# LED_servo_board.net
KiCad netlist of a schematic drawn in EAGLE
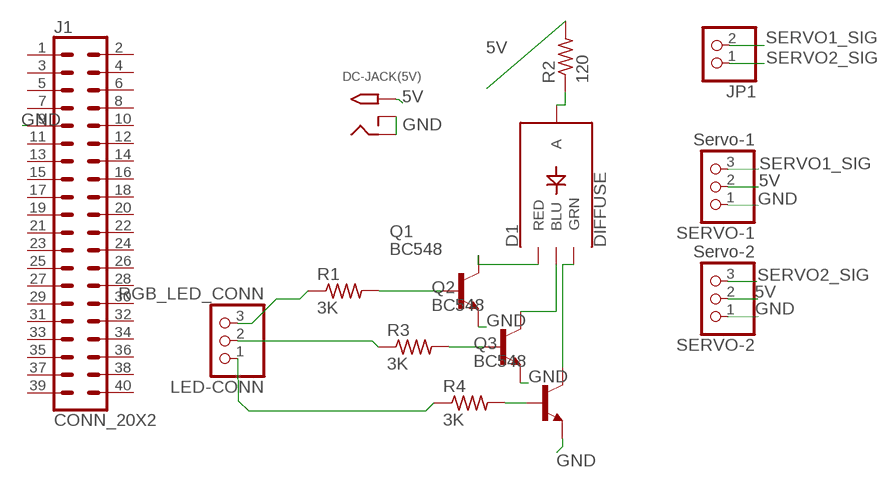
[diagram p0: schematic, sheet 1]

(export (version "E")
  (design (tool "Eeschema 10.0.6"))
  (components
    (comp (ref "D1")
      (value "DIFFUSE")
      (footprint "eagle-import:LED-RGB-THRU")
      (libsource (lib "eagle-import") (part "LED-RGB-CADIFFUSE"))
    )
    (comp (ref "DC-JACK(5V)")
      (value "2.1MMJACKTHM")
      (footprint "eagle-import:PJ-102A")
      (libsource (lib "eagle-import") (part "2.1MMJACKTHM"))
    )
    (comp (ref "J1")
      (value "CONN_20X2")
      (footprint "eagle-import:2X20")
      (libsource (lib "eagle-import") (part "CONN_20X2"))
    )
    (comp (ref "JP1")
      (value "PINHD-1X2")
      (footprint "eagle-import:1X02")
      (libsource (lib "eagle-import") (part "PINHD-1X2"))
    )
    (comp (ref "LED-CONN")
      (value "RGB_LED_CONN")
      (footprint "eagle-import:1X03")
      (libsource (lib "eagle-import") (part "PINHD-1X3"))
    )
    (comp (ref "Q1")
      (value "BC548")
      (footprint "eagle-import:TO92-EBC")
      (libsource (lib "eagle-import") (part "BC548"))
    )
    (comp (ref "Q2")
      (value "BC548")
      (footprint "eagle-import:TO92-EBC")
      (libsource (lib "eagle-import") (part "BC548"))
    )
    (comp (ref "Q3")
      (value "BC548")
      (footprint "eagle-import:TO92-EBC")
      (libsource (lib "eagle-import") (part "BC548"))
    )
    (comp (ref "R1")
      (value "3K")
      (footprint "eagle-import:0204_5")
      (libsource (lib "eagle-import") (part "R-US_0204/5"))
    )
    (comp (ref "R2")
      (value "120")
      (footprint "eagle-import:0204_5")
      (libsource (lib "eagle-import") (part "R-US_0204/5"))
    )
    (comp (ref "R3")
      (value "3K")
      (footprint "eagle-import:0204_5")
      (libsource (lib "eagle-import") (part "R-US_0204/5"))
    )
    (comp (ref "R4")
      (value "3K")
      (footprint "eagle-import:0204_5")
      (libsource (lib "eagle-import") (part "R-US_0204/5"))
    )
    (comp (ref "SERVO-1")
      (value "Servo-1")
      (footprint "eagle-import:1X03")
      (libsource (lib "eagle-import") (part "PINHD-1X3"))
    )
    (comp (ref "SERVO-2")
      (value "Servo-2")
      (footprint "eagle-import:1X03")
      (libsource (lib "eagle-import") (part "PINHD-1X3"))
    )
  )
  (nets
    (net (code "1") (name "/5V") (class "Default")
      (node (ref "DC-JACK(5V)") (pin "TIP") (pinfunction "TIP_TIP") (pintype "bidirectional"))
      (node (ref "R2") (pin "2") (pinfunction "2_2") (pintype "passive"))
      (node (ref "SERVO-1") (pin "2") (pinfunction "2_2") (pintype "passive"))
      (node (ref "SERVO-2") (pin "2") (pinfunction "2_2") (pintype "passive"))
    )
    (net (code "2") (name "/GND") (class "Default")
      (node (ref "DC-JACK(5V)") (pin "RING") (pinfunction "RING_RING") (pintype "bidirectional"))
      (node (ref "DC-JACK(5V)") (pin "RING_SW") (pinfunction "RING_SW_RING_SW") (pintype "bidirectional"))
      (node (ref "J1") (pin "9") (pinfunction "9_9") (pintype "passive"))
      (node (ref "Q1") (pin "E") (pinfunction "E_E") (pintype "passive"))
      (node (ref "Q2") (pin "E") (pinfunction "E_E") (pintype "passive"))
      (node (ref "Q3") (pin "E") (pinfunction "E_E") (pintype "passive"))
      (node (ref "SERVO-1") (pin "1") (pinfunction "1_1") (pintype "passive"))
      (node (ref "SERVO-2") (pin "1") (pinfunction "1_1") (pintype "passive"))
    )
    (net (code "3") (name "/SERVO1_SIG") (class "Default")
      (node (ref "JP1") (pin "2") (pinfunction "2_2") (pintype "passive"))
      (node (ref "SERVO-1") (pin "3") (pinfunction "3_3") (pintype "passive"))
    )
    (net (code "4") (name "/SERVO2_SIG") (class "Default")
      (node (ref "JP1") (pin "1") (pinfunction "1_1") (pintype "passive"))
      (node (ref "SERVO-2") (pin "3") (pinfunction "3_3") (pintype "passive"))
    )
    (net (code "5") (name "Net-(D1-A)") (class "Default")
      (node (ref "D1") (pin "2") (pinfunction "A_2") (pintype "bidirectional"))
      (node (ref "R2") (pin "1") (pinfunction "1_1") (pintype "passive"))
    )
    (net (code "6") (name "Net-(D1-BLU)") (class "Default")
      (node (ref "D1") (pin "4") (pinfunction "BLU_4") (pintype "bidirectional"))
      (node (ref "Q2") (pin "C") (pinfunction "C_C") (pintype "passive"))
    )
    (net (code "7") (name "Net-(D1-GRN)") (class "Default")
      (node (ref "D1") (pin "3") (pinfunction "GRN_3") (pintype "bidirectional"))
      (node (ref "Q3") (pin "C") (pinfunction "C_C") (pintype "passive"))
    )
    (net (code "8") (name "Net-(D1-RED)") (class "Default")
      (node (ref "D1") (pin "1") (pinfunction "RED_1") (pintype "bidirectional"))
      (node (ref "Q1") (pin "C") (pinfunction "C_C") (pintype "passive"))
    )
    (net (code "9") (name "Net-(LED-CONN-Pad1)") (class "Default")
      (node (ref "LED-CONN") (pin "1") (pinfunction "1_1") (pintype "passive"))
      (node (ref "R4") (pin "1") (pinfunction "1_1") (pintype "passive"))
    )
    (net (code "10") (name "Net-(LED-CONN-Pad2)") (class "Default")
      (node (ref "LED-CONN") (pin "2") (pinfunction "2_2") (pintype "passive"))
      (node (ref "R3") (pin "1") (pinfunction "1_1") (pintype "passive"))
    )
    (net (code "11") (name "Net-(LED-CONN-Pad3)") (class "Default")
      (node (ref "LED-CONN") (pin "3") (pinfunction "3_3") (pintype "passive"))
      (node (ref "R1") (pin "1") (pinfunction "1_1") (pintype "passive"))
    )
    (net (code "12") (name "Net-(Q1-PadB)") (class "Default")
      (node (ref "Q1") (pin "B") (pinfunction "B_B") (pintype "passive"))
      (node (ref "R1") (pin "2") (pinfunction "2_2") (pintype "passive"))
    )
    (net (code "13") (name "Net-(Q2-PadB)") (class "Default")
      (node (ref "Q2") (pin "B") (pinfunction "B_B") (pintype "passive"))
      (node (ref "R3") (pin "2") (pinfunction "2_2") (pintype "passive"))
    )
    (net (code "14") (name "Net-(Q3-PadB)") (class "Default")
      (node (ref "Q3") (pin "B") (pinfunction "B_B") (pintype "passive"))
      (node (ref "R4") (pin "2") (pinfunction "2_2") (pintype "passive"))
    )
    (net (code "15") (name "unconnected-(J1-Pad1)") (class "Default")
      (node (ref "J1") (pin "1") (pinfunction "1_1") (pintype "passive"))
    )
    (net (code "16") (name "unconnected-(J1-Pad2)") (class "Default")
      (node (ref "J1") (pin "2") (pinfunction "2_2") (pintype "passive"))
    )
    (net (code "17") (name "unconnected-(J1-Pad3)") (class "Default")
      (node (ref "J1") (pin "3") (pinfunction "3_3") (pintype "passive"))
    )
    (net (code "18") (name "unconnected-(J1-Pad4)") (class "Default")
      (node (ref "J1") (pin "4") (pinfunction "4_4") (pintype "passive"))
    )
    (net (code "19") (name "unconnected-(J1-Pad5)") (class "Default")
      (node (ref "J1") (pin "5") (pinfunction "5_5") (pintype "passive"))
    )
    (net (code "20") (name "unconnected-(J1-Pad6)") (class "Default")
      (node (ref "J1") (pin "6") (pinfunction "6_6") (pintype "passive"))
    )
    (net (code "21") (name "unconnected-(J1-Pad7)") (class "Default")
      (node (ref "J1") (pin "7") (pinfunction "7_7") (pintype "passive"))
    )
    (net (code "22") (name "unconnected-(J1-Pad8)") (class "Default")
      (node (ref "J1") (pin "8") (pinfunction "8_8") (pintype "passive"))
    )
    (net (code "23") (name "unconnected-(J1-Pad10)") (class "Default")
      (node (ref "J1") (pin "10") (pinfunction "10_10") (pintype "passive"))
    )
    (net (code "24") (name "unconnected-(J1-Pad11)") (class "Default")
      (node (ref "J1") (pin "11") (pinfunction "11_11") (pintype "passive"))
    )
    (net (code "25") (name "unconnected-(J1-Pad12)") (class "Default")
      (node (ref "J1") (pin "12") (pinfunction "12_12") (pintype "passive"))
    )
    (net (code "26") (name "unconnected-(J1-Pad13)") (class "Default")
      (node (ref "J1") (pin "13") (pinfunction "13_13") (pintype "passive"))
    )
    (net (code "27") (name "unconnected-(J1-Pad14)") (class "Default")
      (node (ref "J1") (pin "14") (pinfunction "14_14") (pintype "passive"))
    )
    (net (code "28") (name "unconnected-(J1-Pad15)") (class "Default")
      (node (ref "J1") (pin "15") (pinfunction "15_15") (pintype "passive"))
    )
    (net (code "29") (name "unconnected-(J1-Pad16)") (class "Default")
      (node (ref "J1") (pin "16") (pinfunction "16_16") (pintype "passive"))
    )
    (net (code "30") (name "unconnected-(J1-Pad17)") (class "Default")
      (node (ref "J1") (pin "17") (pinfunction "17_17") (pintype "passive"))
    )
    (net (code "31") (name "unconnected-(J1-Pad18)") (class "Default")
      (node (ref "J1") (pin "18") (pinfunction "18_18") (pintype "passive"))
    )
    (net (code "32") (name "unconnected-(J1-Pad19)") (class "Default")
      (node (ref "J1") (pin "19") (pinfunction "19_19") (pintype "passive"))
    )
    (net (code "33") (name "unconnected-(J1-Pad20)") (class "Default")
      (node (ref "J1") (pin "20") (pinfunction "20_20") (pintype "passive"))
    )
    (net (code "34") (name "unconnected-(J1-Pad21)") (class "Default")
      (node (ref "J1") (pin "21") (pinfunction "21_21") (pintype "passive"))
    )
    (net (code "35") (name "unconnected-(J1-Pad22)") (class "Default")
      (node (ref "J1") (pin "22") (pinfunction "22_22") (pintype "passive"))
    )
    (net (code "36") (name "unconnected-(J1-Pad23)") (class "Default")
      (node (ref "J1") (pin "23") (pinfunction "23_23") (pintype "passive"))
    )
    (net (code "37") (name "unconnected-(J1-Pad24)") (class "Default")
      (node (ref "J1") (pin "24") (pinfunction "24_24") (pintype "passive"))
    )
    (net (code "38") (name "unconnected-(J1-Pad25)") (class "Default")
      (node (ref "J1") (pin "25") (pinfunction "25_25") (pintype "passive"))
    )
    (net (code "39") (name "unconnected-(J1-Pad26)") (class "Default")
      (node (ref "J1") (pin "26") (pinfunction "26_26") (pintype "passive"))
    )
    (net (code "40") (name "unconnected-(J1-Pad27)") (class "Default")
      (node (ref "J1") (pin "27") (pinfunction "27_27") (pintype "passive"))
    )
    (net (code "41") (name "unconnected-(J1-Pad28)") (class "Default")
      (node (ref "J1") (pin "28") (pinfunction "28_28") (pintype "passive"))
    )
    (net (code "42") (name "unconnected-(J1-Pad29)") (class "Default")
      (node (ref "J1") (pin "29") (pinfunction "29_29") (pintype "passive"))
    )
    (net (code "43") (name "unconnected-(J1-Pad30)") (class "Default")
      (node (ref "J1") (pin "30") (pinfunction "30_30") (pintype "passive"))
    )
    (net (code "44") (name "unconnected-(J1-Pad31)") (class "Default")
      (node (ref "J1") (pin "31") (pinfunction "31_31") (pintype "passive"))
    )
    (net (code "45") (name "unconnected-(J1-Pad32)") (class "Default")
      (node (ref "J1") (pin "32") (pinfunction "32_32") (pintype "passive"))
    )
    (net (code "46") (name "unconnected-(J1-Pad33)") (class "Default")
      (node (ref "J1") (pin "33") (pinfunction "33_33") (pintype "passive"))
    )
    (net (code "47") (name "unconnected-(J1-Pad34)") (class "Default")
      (node (ref "J1") (pin "34") (pinfunction "34_34") (pintype "passive"))
    )
    (net (code "48") (name "unconnected-(J1-Pad35)") (class "Default")
      (node (ref "J1") (pin "35") (pinfunction "35_35") (pintype "passive"))
    )
    (net (code "49") (name "unconnected-(J1-Pad36)") (class "Default")
      (node (ref "J1") (pin "36") (pinfunction "36_36") (pintype "passive"))
    )
    (net (code "50") (name "unconnected-(J1-Pad37)") (class "Default")
      (node (ref "J1") (pin "37") (pinfunction "37_37") (pintype "passive"))
    )
    (net (code "51") (name "unconnected-(J1-Pad38)") (class "Default")
      (node (ref "J1") (pin "38") (pinfunction "38_38") (pintype "passive"))
    )
    (net (code "52") (name "unconnected-(J1-Pad39)") (class "Default")
      (node (ref "J1") (pin "39") (pinfunction "39_39") (pintype "passive"))
    )
    (net (code "53") (name "unconnected-(J1-Pad40)") (class "Default")
      (node (ref "J1") (pin "40") (pinfunction "40_40") (pintype "passive"))
    )
  )
)
